# ProPrj__1__2025-03-03.net
KiCad netlist of a schematic drawn in EasyEDA Pro
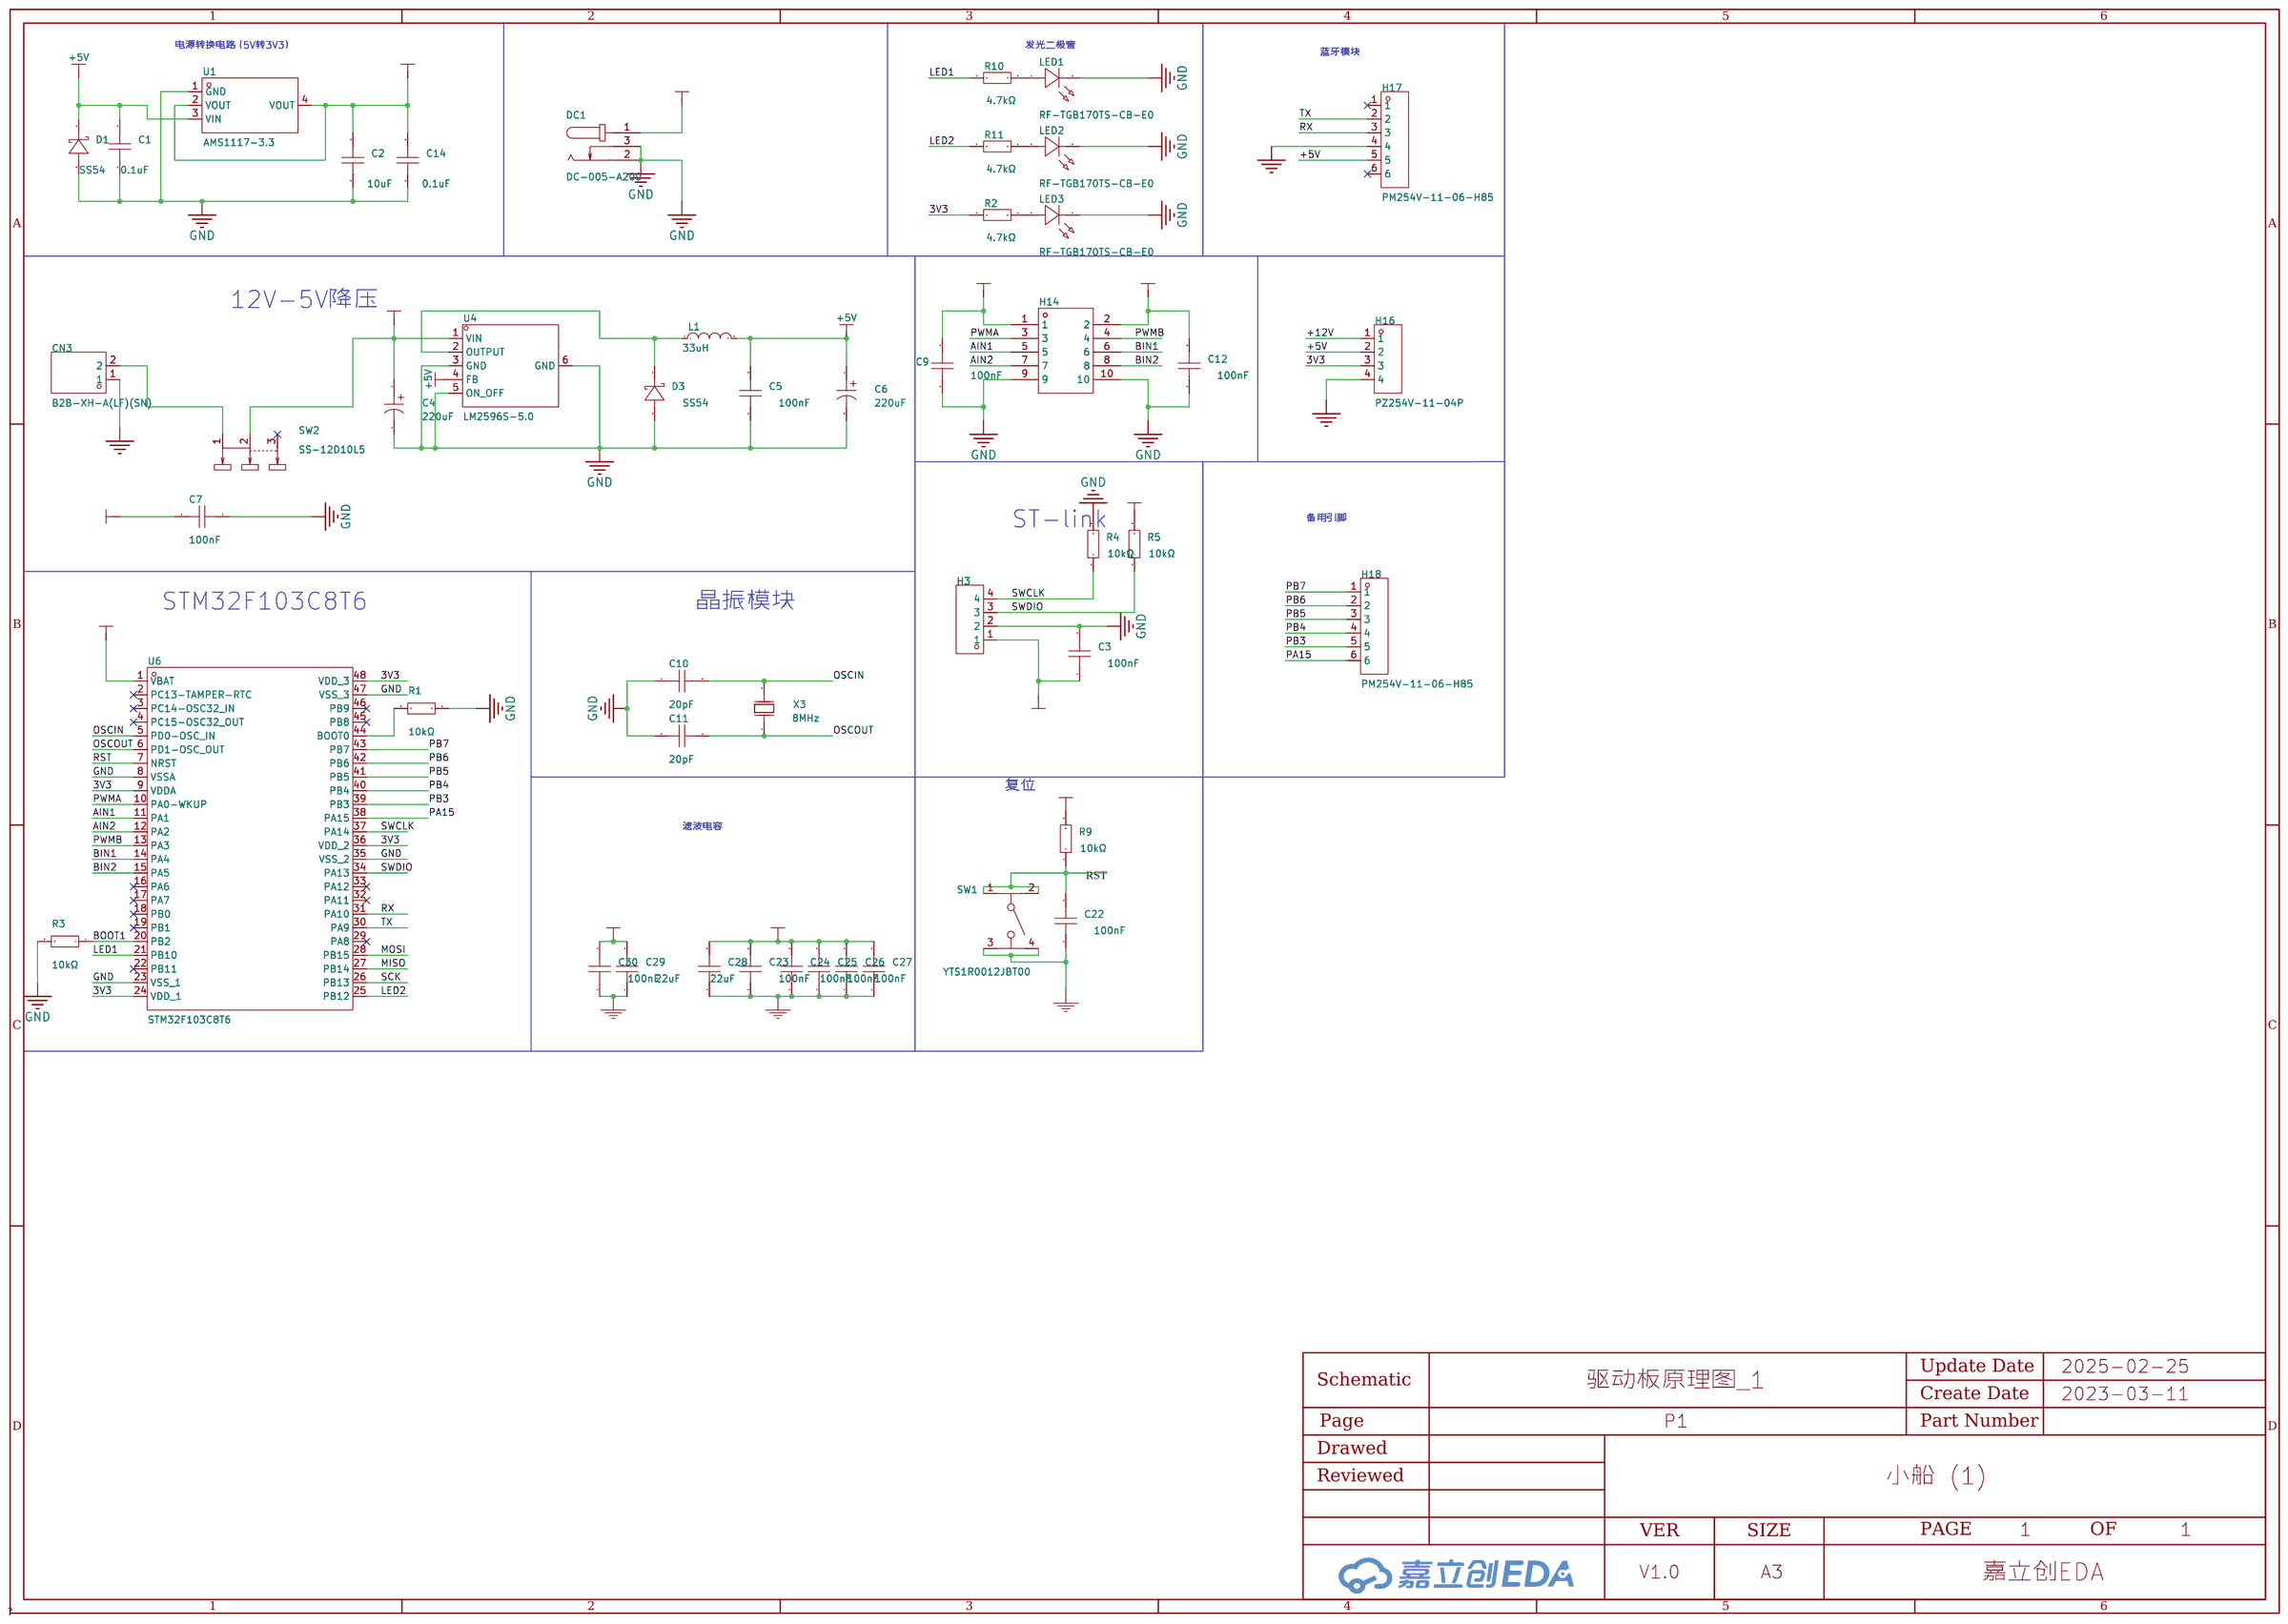
[diagram p0: schematic sheet]

(export (version "E")
  (design (tool "Eeschema 10.0.6"))
  (components
    (comp (ref "C1")
      (value "0.1uF")
      (footprint "easyedapro:C1206")
      (description "容值:47uF;精度:±20%;额定电压:16V;材质(温度系数):X5R;")
      (fields
        (field (name "Manufacturer Part") "GRM31CR61C476ME44L")
        (field (name "Manufacturer") "muRata(村田)")
      )
      (libsource (lib "easyedapro") (part "GRM31CR61C476ME44L"))
    )
    (comp (ref "C2")
      (value "10uF")
      (footprint "easyedapro:C0805")
      (description "温度系数:X7R;容值:100nF;精度:±10%;额定电压:100V;")
      (fields (field (name "Manufacturer Part") "C0805X104K101T") (field (name "Manufacturer") "IHHEC(禾伸堂)"))
      (libsource (lib "easyedapro") (part "C0805X104K101T_C485772"))
    )
    (comp (ref "C3")
      (value "100nF")
      (footprint "easyedapro:C0603")
      (description "容值:100nF;精度:-20%~+80%;额定电压:50V;材质(温度系数):Y5V;")
      (fields (field (name "Manufacturer Part") "0603F104Z500CT") (field (name "Manufacturer") "Walsin(华新科)"))
      (libsource (lib "easyedapro") (part "0603F104Z500"))
    )
    (comp (ref "C4")
      (value "220uF")
      (footprint "easyedapro:CAP-SMD_BD6.3-L6.6-W6.6-FD")
      (description "容值:220uF;额定电压:25V;")
      (fields
        (field (name "Manufacturer Part") "RX220UF25V90RV0108")
        (field (name "Manufacturer") "KNSCHA(科尼盛)")
      )
      (libsource (lib "easyedapro") (part "RX220UF25V90RV0108"))
    )
    (comp (ref "C5")
      (value "100nF")
      (footprint "easyedapro:C0805")
      (description "温度系数:X7R;容值:100nF;精度:±10%;额定电压:100V;")
      (fields (field (name "Manufacturer Part") "C0805X104K101T") (field (name "Manufacturer") "IHHEC(禾伸堂)"))
      (libsource (lib "easyedapro") (part "C0805X104K101T_C485772"))
    )
    (comp (ref "C6")
      (value "220uF")
      (footprint "easyedapro:CAP-SMD_BD6.3-L6.6-W6.6-FD")
      (description "容值:220uF;额定电压:25V;")
      (fields
        (field (name "Manufacturer Part") "RX220UF25V90RV0108")
        (field (name "Manufacturer") "KNSCHA(科尼盛)")
      )
      (libsource (lib "easyedapro") (part "RX220UF25V90RV0108"))
    )
    (comp (ref "C7")
      (value "100nF")
      (footprint "easyedapro:C0805")
      (description "温度系数:X7R;容值:100nF;精度:±10%;额定电压:100V;")
      (fields (field (name "Manufacturer Part") "C0805X104K101T") (field (name "Manufacturer") "IHHEC(禾伸堂)"))
      (libsource (lib "easyedapro") (part "C0805X104K101T_C485772"))
    )
    (comp (ref "C9")
      (value "100nF")
      (footprint "easyedapro:C0805")
      (description "温度系数:X7R;容值:100nF;精度:±10%;额定电压:100V;")
      (fields (field (name "Manufacturer Part") "C0805X104K101T") (field (name "Manufacturer") "IHHEC(禾伸堂)"))
      (libsource (lib "easyedapro") (part "C0805X104K101T_C485772"))
    )
    (comp (ref "C10")
      (value "20pF")
      (footprint "easyedapro:C0603")
      (description "容值:20pF;精度:±5%;额定电压:100V;材质(温度系数):C0G;额定电压(VAC):-;")
      (fields (field (name "Manufacturer Part") "0603CG200J101NT") (field (name "Manufacturer") "FH(风华)"))
      (libsource (lib "easyedapro") (part "0603CG200J101NT"))
    )
    (comp (ref "C11")
      (value "20pF")
      (footprint "easyedapro:C0603")
      (description "容值:20pF;精度:±5%;额定电压:100V;材质(温度系数):C0G;额定电压(VAC):-;")
      (fields (field (name "Manufacturer Part") "0603CG200J101NT") (field (name "Manufacturer") "FH(风华)"))
      (libsource (lib "easyedapro") (part "0603CG200J101NT"))
    )
    (comp (ref "C12")
      (value "100nF")
      (footprint "easyedapro:C0805")
      (description "温度系数:X7R;容值:100nF;精度:±10%;额定电压:100V;")
      (fields (field (name "Manufacturer Part") "C0805X104K101T") (field (name "Manufacturer") "IHHEC(禾伸堂)"))
      (libsource (lib "easyedapro") (part "C0805X104K101T_C485772"))
    )
    (comp (ref "C14")
      (value "0.1uF")
      (footprint "easyedapro:C1206")
      (description "容值:47uF;精度:±20%;额定电压:16V;材质(温度系数):X5R;")
      (fields
        (field (name "Manufacturer Part") "GRM31CR61C476ME44L")
        (field (name "Manufacturer") "muRata(村田)")
      )
      (libsource (lib "easyedapro") (part "GRM31CR61C476ME44L"))
    )
    (comp (ref "C22")
      (value "100nF")
      (footprint "easyedapro:C0603")
      (description "容值:100nF;精度:-20%~+80%;额定电压:50V;材质(温度系数):Y5V;")
      (fields (field (name "Manufacturer Part") "0603F104Z500CT") (field (name "Manufacturer") "Walsin(华新科)"))
      (libsource (lib "easyedapro") (part "0603F104Z500"))
    )
    (comp (ref "C23")
      (value "100nF")
      (footprint "easyedapro:C0603")
      (description "容值:100nF;精度:-20%~+80%;额定电压:50V;材质(温度系数):Y5V;")
      (fields (field (name "Manufacturer Part") "0603F104Z500CT") (field (name "Manufacturer") "Walsin(华新科)"))
      (libsource (lib "easyedapro") (part "0603F104Z500"))
    )
    (comp (ref "C24")
      (value "100nF")
      (footprint "easyedapro:C0603")
      (description "容值:100nF;精度:-20%~+80%;额定电压:50V;材质(温度系数):Y5V;")
      (fields (field (name "Manufacturer Part") "0603F104Z500CT") (field (name "Manufacturer") "Walsin(华新科)"))
      (libsource (lib "easyedapro") (part "0603F104Z500"))
    )
    (comp (ref "C25")
      (value "100nF")
      (footprint "easyedapro:C0603")
      (description "容值:100nF;精度:-20%~+80%;额定电压:50V;材质(温度系数):Y5V;")
      (fields (field (name "Manufacturer Part") "0603F104Z500CT") (field (name "Manufacturer") "Walsin(华新科)"))
      (libsource (lib "easyedapro") (part "0603F104Z500"))
    )
    (comp (ref "C26")
      (value "100nF")
      (footprint "easyedapro:C0603")
      (description "容值:100nF;精度:-20%~+80%;额定电压:50V;材质(温度系数):Y5V;")
      (fields (field (name "Manufacturer Part") "0603F104Z500CT") (field (name "Manufacturer") "Walsin(华新科)"))
      (libsource (lib "easyedapro") (part "0603F104Z500"))
    )
    (comp (ref "C27")
      (value "100nF")
      (footprint "easyedapro:C0603")
      (description "容值:100nF;精度:-20%~+80%;额定电压:50V;材质(温度系数):Y5V;")
      (fields (field (name "Manufacturer Part") "0603F104Z500CT") (field (name "Manufacturer") "Walsin(华新科)"))
      (libsource (lib "easyedapro") (part "0603F104Z500"))
    )
    (comp (ref "C28")
      (value "22uF")
      (footprint "easyedapro:C0603")
      (description "容值:22uF;精度:±20%;额定电压:4V;材质(温度系数):X5R;")
      (fields
        (field (name "Manufacturer Part") "CL10A226MR8NQNC")
        (field (name "Manufacturer") "SAMSUNG(三星)")
      )
      (libsource (lib "easyedapro") (part "CL10A226MR8NQNC"))
    )
    (comp (ref "C29")
      (value "22uF")
      (footprint "easyedapro:C0603")
      (description "容值:22uF;精度:±20%;额定电压:4V;材质(温度系数):X5R;")
      (fields
        (field (name "Manufacturer Part") "CL10A226MR8NQNC")
        (field (name "Manufacturer") "SAMSUNG(三星)")
      )
      (libsource (lib "easyedapro") (part "CL10A226MR8NQNC"))
    )
    (comp (ref "C30")
      (value "100nF")
      (footprint "easyedapro:C0603")
      (description "容值:100nF;精度:-20%~+80%;额定电压:50V;材质(温度系数):Y5V;")
      (fields (field (name "Manufacturer Part") "0603F104Z500CT") (field (name "Manufacturer") "Walsin(华新科)"))
      (libsource (lib "easyedapro") (part "0603F104Z500"))
    )
    (comp (ref "CN3")
      (value "B2B-XH-A(LF)(SN)")
      (footprint "easyedapro:CONN-TH_B2B-XH-A-LF-SN")
      (fields (field (name "Manufacturer") "JST"))
      (libsource (lib "easyedapro") (part "B2B-XH-A (LF)(SN)"))
    )
    (comp (ref "D1")
      (value "SS54")
      (footprint "easyedapro:SMA_L4.3-W2.6-LS5.0-RD")
      (fields (field (name "Manufacturer") "TWGMC(台湾迪嘉)"))
      (libsource (lib "easyedapro") (part "SS54_C727065"))
    )
    (comp (ref "D3")
      (value "SS54")
      (footprint "easyedapro:SMA_L4.3-W2.6-LS5.0-RD")
      (fields (field (name "Manufacturer") "TWGMC(台湾迪嘉)"))
      (libsource (lib "easyedapro") (part "SS54_C727065"))
    )
    (comp (ref "DC1")
      (value "DC-005-A200")
      (footprint "easyedapro:DC-IN-TH_DC-005-A200")
      (description "连接器类型:DC电源插座;安装方式:弯插;触点内径:2mm;触点外径:6.4mm;额定电流:3A;额定电压:30V;工作温度范围:-20°C~+70°C;")
      (fields (field (name "Manufacturer") "XUNPU(讯普)"))
      (libsource (lib "easyedapro") (part "DC-005-A200"))
    )
    (comp (ref "H3")
      (value "~")
      (footprint "easyedapro:HDR-TH_4P-P2.54-V-M")
      (libsource (lib "easyedapro") (part "PZ254V-11-04P"))
    )
    (comp (ref "H14")
      (value "~")
      (footprint "easyedapro:HDR-TH_10P-P2.54-V-M-R2-C5-S2.54")
      (libsource (lib "easyedapro") (part "HDR-M-2.54_2x5"))
    )
    (comp (ref "H16")
      (value "PZ254V-11-04P")
      (footprint "easyedapro:HDR-TH_4P-P2.54-V-M")
      (fields (field (name "Manufacturer") "XFCN(兴飞)"))
      (libsource (lib "easyedapro") (part "PZ254V-11-04P_C2691448"))
    )
    (comp (ref "H17")
      (value "PM254V-11-06-H85")
      (footprint "easyedapro:HDR-TH_6P-P2.54-V-F")
      (fields (field (name "Manufacturer") "XFCN(兴飞)"))
      (libsource (lib "easyedapro") (part "PM254V-11-06-H85"))
    )
    (comp (ref "H18")
      (value "PM254V-11-06-H85")
      (footprint "easyedapro:HDR-TH_6P-P2.54-V-F")
      (fields (field (name "Manufacturer") "XFCN(兴飞)"))
      (libsource (lib "easyedapro") (part "PM254V-11-06-H85"))
    )
    (comp (ref "L1")
      (value "33uH")
      (footprint "easyedapro:IND-SMD_L7.5-W7.5_CYH74")
      (description "电感值:33uH;精度:±20%;额定电流:-;饱和电流(Isat):-;直流电阻(DCR):-;类型:-;")
      (fields (field (name "Manufacturer Part") "CYH74-33UH") (field (name "Manufacturer") "SHOU HAN(首韩)"))
      (libsource (lib "easyedapro") (part "CYH74-33UH"))
    )
    (comp (ref "LED1")
      (value "RF-TGB170TS-CB-E0")
      (footprint "easyedapro:LED0805-R-RD")
      (description "发光颜色:翠绿;二极管配置:-;透镜颜色:-;主波长:-;峰值波长:-;色温:-;测试电流:20mA;功率:105mW;发光角度:140°;安装方式:正贴;工作温度:-40°C~+85°C;")
      (fields (field (name "Manufacturer") "Refond(瑞丰)"))
      (libsource (lib "easyedapro") (part "RF-TGB170TS-CB-E0"))
    )
    (comp (ref "LED2")
      (value "RF-TGB170TS-CB-E0")
      (footprint "easyedapro:LED0805-R-RD")
      (description "发光颜色:翠绿;二极管配置:-;透镜颜色:-;主波长:-;峰值波长:-;色温:-;测试电流:20mA;功率:105mW;发光角度:140°;安装方式:正贴;工作温度:-40°C~+85°C;")
      (fields (field (name "Manufacturer") "Refond(瑞丰)"))
      (libsource (lib "easyedapro") (part "RF-TGB170TS-CB-E0"))
    )
    (comp (ref "LED3")
      (value "RF-TGB170TS-CB-E0")
      (footprint "easyedapro:LED0805-R-RD")
      (description "发光颜色:翠绿;二极管配置:-;透镜颜色:-;主波长:-;峰值波长:-;色温:-;测试电流:20mA;功率:105mW;发光角度:140°;安装方式:正贴;工作温度:-40°C~+85°C;")
      (fields (field (name "Manufacturer") "Refond(瑞丰)"))
      (libsource (lib "easyedapro") (part "RF-TGB170TS-CB-E0"))
    )
    (comp (ref "R1")
      (value "10kΩ")
      (footprint "easyedapro:R0603")
      (description "精度:±1%;阻值:10kΩ;功率:1/10W;电阻类型:厚膜电阻;最大工作电压:75V;工作温度范围:-55°C~+155°C;")
      (fields (field (name "Manufacturer Part") "CR-03FA7---10K") (field (name "Manufacturer") "Viking(光颉)"))
      (libsource (lib "easyedapro") (part "CR-03FA7---10K"))
    )
    (comp (ref "R2")
      (value "4.7kΩ")
      (footprint "easyedapro:R0805")
      (description "阻值:4.7kΩ;精度:±1%;功率:125mW;")
      (fields (field (name "Manufacturer Part") "RMC08054.7K1%N") (field (name "Manufacturer") "Tyohm(幸亚电阻)"))
      (libsource (lib "easyedapro") (part "RMC08054.7K1%N"))
    )
    (comp (ref "R3")
      (value "10kΩ")
      (footprint "easyedapro:R0603")
      (description "精度:±1%;阻值:10kΩ;功率:1/10W;电阻类型:厚膜电阻;最大工作电压:75V;工作温度范围:-55°C~+155°C;")
      (fields (field (name "Manufacturer Part") "CR-03FA7---10K") (field (name "Manufacturer") "Viking(光颉)"))
      (libsource (lib "easyedapro") (part "CR-03FA7---10K"))
    )
    (comp (ref "R4")
      (value "10kΩ")
      (footprint "easyedapro:R0805")
      (description "电阻类型:厚膜电阻;阻值:10kΩ;精度:±0.5%;功率:125mW;温度系数:±100ppm/°C;最大工作电压:150V;工作温度范围:-55°C~+155°C;")
      (fields (field (name "Manufacturer Part") "RC0805DR-0710KL") (field (name "Manufacturer") "YAGEO(国巨)"))
      (libsource (lib "easyedapro") (part "RC0805DR-0710KL"))
    )
    (comp (ref "R5")
      (value "10kΩ")
      (footprint "easyedapro:R0805")
      (description "电阻类型:厚膜电阻;阻值:10kΩ;精度:±0.5%;功率:125mW;温度系数:±100ppm/°C;最大工作电压:150V;工作温度范围:-55°C~+155°C;")
      (fields (field (name "Manufacturer Part") "RC0805DR-0710KL") (field (name "Manufacturer") "YAGEO(国巨)"))
      (libsource (lib "easyedapro") (part "RC0805DR-0710KL"))
    )
    (comp (ref "R9")
      (value "10kΩ")
      (footprint "easyedapro:R0805")
      (description "电阻类型:厚膜电阻;阻值:10kΩ;精度:±0.5%;功率:125mW;温度系数:±100ppm/°C;最大工作电压:150V;工作温度范围:-55°C~+155°C;")
      (fields (field (name "Manufacturer Part") "RC0805DR-0710KL") (field (name "Manufacturer") "YAGEO(国巨)"))
      (libsource (lib "easyedapro") (part "RC0805DR-0710KL"))
    )
    (comp (ref "R10")
      (value "4.7kΩ")
      (footprint "easyedapro:R0805")
      (description "阻值:4.7kΩ;精度:±1%;功率:125mW;")
      (fields (field (name "Manufacturer Part") "RMC08054.7K1%N") (field (name "Manufacturer") "Tyohm(幸亚电阻)"))
      (libsource (lib "easyedapro") (part "RMC08054.7K1%N"))
    )
    (comp (ref "R11")
      (value "4.7kΩ")
      (footprint "easyedapro:R0805")
      (description "阻值:4.7kΩ;精度:±1%;功率:125mW;")
      (fields (field (name "Manufacturer Part") "RMC08054.7K1%N") (field (name "Manufacturer") "Tyohm(幸亚电阻)"))
      (libsource (lib "easyedapro") (part "RMC08054.7K1%N"))
    )
    (comp (ref "SW1")
      (value "YTS1R0012JBT00")
      (footprint "easyedapro:SW-TH_4P-L6.0-W6.0-P4.50-LS6.5")
      (fields (field (name "Manufacturer") "YIYUAN(怡远)"))
      (libsource (lib "easyedapro") (part "YTS1R0012JBT00"))
    )
    (comp (ref "SW2")
      (value "SS-12D10L5")
      (footprint "easyedapro:SW-TH_SS-12D10L5")
      (description "电路结构:单刀双掷;安装方式:直插;开关颜色:黑色;额定电流(DC):3A;额定电压(DC):125V;额定电流(AC):3A;额定电压(AC):125V;机械寿命:1万次;")
      (fields (field (name "Manufacturer") "XKB Connectivity(中国星坤)"))
      (libsource (lib "easyedapro") (part "SS-12D10L5"))
    )
    (comp (ref "U1")
      (value "AMS1117-3.3")
      (footprint "easyedapro:SOT-223-3_L6.5-W3.4-P2.30-LS7.0-BR")
      (fields (field (name "Manufacturer") "美国AMS"))
      (libsource (lib "easyedapro") (part "AMS1117-3.3"))
    )
    (comp (ref "U4")
      (value "LM2596S-5.0")
      (footprint "easyedapro:TO-263-5_L10.1-W8.7-P1.70-LS14.4-BR")
      (fields (field (name "Manufacturer") "Slkor(萨科微)"))
      (libsource (lib "easyedapro") (part "LM2596S-5.0_C2980820"))
    )
    (comp (ref "U6")
      (value "STM32F103C8T6")
      (footprint "easyedapro:LQFP-48_L7.0-W7.0-P0.50-LS9.0-BL")
      (fields (field (name "Manufacturer") "ST(意法半导体)"))
      (libsource (lib "easyedapro") (part "STM32F103C8T6"))
    )
    (comp (ref "X3")
      (value "8MHz")
      (footprint "easyedapro:HC-49US_L11.0-W4.6-P4.88")
      (description "晶振类型:49S晶振;频率:8MHz;频率公差:±20ppm;频率稳定度:±30ppm;负载电容:18pF;等效串联电阻(ESR):60Ω;工作温度:-40°C~+85°C;")
      (fields (field (name "Manufacturer Part") "49SAC08000182060") (field (name "Manufacturer") "JGHC(晶光华)"))
      (libsource (lib "easyedapro") (part "49SAC08000182060"))
    )
  )
  (nets
    (net (code "1") (name "+5V") (class "Default")
      (node (ref "C1") (pin "2") (pinfunction "2_2") (pintype "input"))
      (node (ref "C29") (pin "2") (pinfunction "2_2") (pintype "input"))
      (node (ref "C30") (pin "2") (pinfunction "2_2") (pintype "input"))
      (node (ref "C5") (pin "2") (pinfunction "2_2") (pintype "input"))
      (node (ref "C6") (pin "1") (pinfunction "1_1") (pintype "input"))
      (node (ref "D1") (pin "1") (pinfunction "1_1") (pintype "input"))
      (node (ref "H16") (pin "2") (pinfunction "2_2") (pintype "unspecified"))
      (node (ref "H17") (pin "5") (pinfunction "5_5") (pintype "unspecified"))
      (node (ref "L1") (pin "2") (pinfunction "2_2") (pintype "input"))
      (node (ref "U1") (pin "3") (pinfunction "VIN_3") (pintype "input"))
      (node (ref "U4") (pin "4") (pinfunction "FB_4") (pintype "input"))
    )
    (net (code "2") (name "+12V") (class "Default")
      (node (ref "C4") (pin "1") (pinfunction "1_1") (pintype "input"))
      (node (ref "C7") (pin "2") (pinfunction "2_2") (pintype "input"))
      (node (ref "DC1") (pin "1") (pinfunction "1_1") (pintype "unspecified"))
      (node (ref "H16") (pin "1") (pinfunction "1_1") (pintype "unspecified"))
      (node (ref "SW2") (pin "2") (pinfunction "2_2") (pintype "unspecified"))
      (node (ref "U4") (pin "1") (pinfunction "VIN_1") (pintype "input"))
    )
    (net (code "3") (name "/AIN1") (class "Default")
      (node (ref "H14") (pin "5") (pinfunction "5_5") (pintype "input"))
      (node (ref "U6") (pin "11") (pinfunction "PA1_11") (pintype "input"))
    )
    (net (code "4") (name "/AIN2") (class "Default")
      (node (ref "H14") (pin "7") (pinfunction "7_7") (pintype "input"))
      (node (ref "U6") (pin "12") (pinfunction "PA2_12") (pintype "input"))
    )
    (net (code "5") (name "/BIN1") (class "Default")
      (node (ref "H14") (pin "6") (pinfunction "6_6") (pintype "input"))
      (node (ref "U6") (pin "14") (pinfunction "PA4_14") (pintype "input"))
    )
    (net (code "6") (name "/BIN2") (class "Default")
      (node (ref "H14") (pin "8") (pinfunction "8_8") (pintype "input"))
      (node (ref "U6") (pin "15") (pinfunction "PA5_15") (pintype "input"))
    )
    (net (code "7") (name "/BOOT1") (class "Default")
      (node (ref "R3") (pin "1") (pinfunction "1_1") (pintype "input"))
      (node (ref "U6") (pin "20") (pinfunction "PB2_20") (pintype "input"))
    )
    (net (code "8") (name "/LED1") (class "Default")
      (node (ref "R10") (pin "1") (pinfunction "1_1") (pintype "input"))
      (node (ref "U6") (pin "21") (pinfunction "PB10_21") (pintype "input"))
    )
    (net (code "9") (name "/LED2") (class "Default")
      (node (ref "R11") (pin "1") (pinfunction "1_1") (pintype "input"))
      (node (ref "U6") (pin "25") (pinfunction "PB12_25") (pintype "input"))
    )
    (net (code "10") (name "/MISO") (class "Default")
      (node (ref "U6") (pin "27") (pinfunction "PB14_27") (pintype "input"))
    )
    (net (code "11") (name "/MOSI") (class "Default")
      (node (ref "U6") (pin "28") (pinfunction "PB15_28") (pintype "input"))
    )
    (net (code "12") (name "/OSCIN") (class "Default")
      (node (ref "C10") (pin "2") (pinfunction "2_2") (pintype "input"))
      (node (ref "U6") (pin "5") (pinfunction "PD0-OSC_IN_5") (pintype "input"))
      (node (ref "X3") (pin "2") (pinfunction "OSC2_2") (pintype "input"))
    )
    (net (code "13") (name "/OSCOUT") (class "Default")
      (node (ref "C11") (pin "2") (pinfunction "2_2") (pintype "input"))
      (node (ref "U6") (pin "6") (pinfunction "PD1-OSC_OUT_6") (pintype "input"))
      (node (ref "X3") (pin "1") (pinfunction "OSC1_1") (pintype "input"))
    )
    (net (code "14") (name "/PA15") (class "Default")
      (node (ref "H18") (pin "6") (pinfunction "6_6") (pintype "unspecified"))
      (node (ref "U6") (pin "38") (pinfunction "PA15_38") (pintype "input"))
    )
    (net (code "15") (name "/PB3") (class "Default")
      (node (ref "H18") (pin "5") (pinfunction "5_5") (pintype "unspecified"))
      (node (ref "U6") (pin "39") (pinfunction "PB3_39") (pintype "input"))
    )
    (net (code "16") (name "/PB4") (class "Default")
      (node (ref "H18") (pin "4") (pinfunction "4_4") (pintype "unspecified"))
      (node (ref "U6") (pin "40") (pinfunction "PB4_40") (pintype "input"))
    )
    (net (code "17") (name "/PB5") (class "Default")
      (node (ref "H18") (pin "3") (pinfunction "3_3") (pintype "unspecified"))
      (node (ref "U6") (pin "41") (pinfunction "PB5_41") (pintype "input"))
    )
    (net (code "18") (name "/PB6") (class "Default")
      (node (ref "H18") (pin "2") (pinfunction "2_2") (pintype "unspecified"))
      (node (ref "U6") (pin "42") (pinfunction "PB6_42") (pintype "input"))
    )
    (net (code "19") (name "/PB7") (class "Default")
      (node (ref "H18") (pin "1") (pinfunction "1_1") (pintype "unspecified"))
      (node (ref "U6") (pin "43") (pinfunction "PB7_43") (pintype "input"))
    )
    (net (code "20") (name "/PWMA") (class "Default")
      (node (ref "H14") (pin "3") (pinfunction "3_3") (pintype "input"))
      (node (ref "U6") (pin "10") (pinfunction "PA0-WKUP_10") (pintype "input"))
    )
    (net (code "21") (name "/PWMB") (class "Default")
      (node (ref "H14") (pin "4") (pinfunction "4_4") (pintype "input"))
      (node (ref "U6") (pin "13") (pinfunction "PA3_13") (pintype "input"))
    )
    (net (code "22") (name "/RST") (class "Default")
      (node (ref "C22") (pin "2") (pinfunction "2_2") (pintype "input"))
      (node (ref "R9") (pin "1") (pinfunction "1_1") (pintype "input"))
      (node (ref "SW1") (pin "1") (pinfunction "1_1") (pintype "input"))
      (node (ref "SW1") (pin "2") (pinfunction "2_2") (pintype "input"))
      (node (ref "U6") (pin "7") (pinfunction "NRST_7") (pintype "input"))
    )
    (net (code "23") (name "/RX") (class "Default")
      (node (ref "H17") (pin "3") (pinfunction "3_3") (pintype "unspecified"))
      (node (ref "U6") (pin "31") (pinfunction "PA10_31") (pintype "input"))
    )
    (net (code "24") (name "/SCK") (class "Default")
      (node (ref "U6") (pin "26") (pinfunction "PB13_26") (pintype "input"))
    )
    (net (code "25") (name "/SWCLK") (class "Default")
      (node (ref "H3") (pin "4") (pinfunction "4_4") (pintype "input"))
      (node (ref "R4") (pin "1") (pinfunction "1_1") (pintype "input"))
      (node (ref "U6") (pin "37") (pinfunction "PA14_37") (pintype "input"))
    )
    (net (code "26") (name "/SWDIO") (class "Default")
      (node (ref "H3") (pin "3") (pinfunction "3_3") (pintype "input"))
      (node (ref "R5") (pin "1") (pinfunction "1_1") (pintype "input"))
      (node (ref "U6") (pin "34") (pinfunction "PA13_34") (pintype "input"))
    )
    (net (code "27") (name "/TX") (class "Default")
      (node (ref "H17") (pin "2") (pinfunction "2_2") (pintype "unspecified"))
      (node (ref "U6") (pin "30") (pinfunction "PA9_30") (pintype "input"))
    )
    (net (code "28") (name "3V3") (class "Default")
      (node (ref "C12") (pin "2") (pinfunction "2_2") (pintype "input"))
      (node (ref "C14") (pin "2") (pinfunction "2_2") (pintype "input"))
      (node (ref "C2") (pin "2") (pinfunction "2_2") (pintype "input"))
      (node (ref "C23") (pin "2") (pinfunction "2_2") (pintype "input"))
      (node (ref "C24") (pin "2") (pinfunction "2_2") (pintype "input"))
      (node (ref "C25") (pin "2") (pinfunction "2_2") (pintype "input"))
      (node (ref "C26") (pin "2") (pinfunction "2_2") (pintype "input"))
      (node (ref "C27") (pin "2") (pinfunction "2_2") (pintype "input"))
      (node (ref "C28") (pin "2") (pinfunction "2_2") (pintype "input"))
      (node (ref "C3") (pin "1") (pinfunction "1_1") (pintype "input"))
      (node (ref "C9") (pin "2") (pinfunction "2_2") (pintype "input"))
      (node (ref "H14") (pin "1") (pinfunction "1_1") (pintype "input"))
      (node (ref "H14") (pin "2") (pinfunction "2_2") (pintype "input"))
      (node (ref "H16") (pin "3") (pinfunction "3_3") (pintype "unspecified"))
      (node (ref "H3") (pin "1") (pinfunction "1_1") (pintype "input"))
      (node (ref "R2") (pin "1") (pinfunction "1_1") (pintype "input"))
      (node (ref "R5") (pin "2") (pinfunction "2_2") (pintype "input"))
      (node (ref "R9") (pin "2") (pinfunction "2_2") (pintype "input"))
      (node (ref "U1") (pin "2") (pinfunction "VOUT_2") (pintype "input"))
      (node (ref "U1") (pin "4") (pinfunction "VOUT_4") (pintype "input"))
      (node (ref "U6") (pin "1") (pinfunction "VBAT_1") (pintype "input"))
      (node (ref "U6") (pin "24") (pinfunction "VDD_1_24") (pintype "input"))
      (node (ref "U6") (pin "36") (pinfunction "VDD_2_36") (pintype "input"))
      (node (ref "U6") (pin "48") (pinfunction "VDD_3_48") (pintype "input"))
      (node (ref "U6") (pin "9") (pinfunction "VDDA_9") (pintype "input"))
    )
    (net (code "29") (name "GND") (class "Default")
      (node (ref "C1") (pin "1") (pinfunction "1_1") (pintype "input"))
      (node (ref "C10") (pin "1") (pinfunction "1_1") (pintype "input"))
      (node (ref "C11") (pin "1") (pinfunction "1_1") (pintype "input"))
      (node (ref "C12") (pin "1") (pinfunction "1_1") (pintype "input"))
      (node (ref "C14") (pin "1") (pinfunction "1_1") (pintype "input"))
      (node (ref "C2") (pin "1") (pinfunction "1_1") (pintype "input"))
      (node (ref "C22") (pin "1") (pinfunction "1_1") (pintype "input"))
      (node (ref "C23") (pin "1") (pinfunction "1_1") (pintype "input"))
      (node (ref "C24") (pin "1") (pinfunction "1_1") (pintype "input"))
      (node (ref "C25") (pin "1") (pinfunction "1_1") (pintype "input"))
      (node (ref "C26") (pin "1") (pinfunction "1_1") (pintype "input"))
      (node (ref "C27") (pin "1") (pinfunction "1_1") (pintype "input"))
      (node (ref "C28") (pin "1") (pinfunction "1_1") (pintype "input"))
      (node (ref "C29") (pin "1") (pinfunction "1_1") (pintype "input"))
      (node (ref "C3") (pin "2") (pinfunction "2_2") (pintype "input"))
      (node (ref "C30") (pin "1") (pinfunction "1_1") (pintype "input"))
      (node (ref "C4") (pin "2") (pinfunction "2_2") (pintype "input"))
      (node (ref "C5") (pin "1") (pinfunction "1_1") (pintype "input"))
      (node (ref "C6") (pin "2") (pinfunction "2_2") (pintype "input"))
      (node (ref "C7") (pin "1") (pinfunction "1_1") (pintype "input"))
      (node (ref "C9") (pin "1") (pinfunction "1_1") (pintype "input"))
      (node (ref "CN3") (pin "1") (pinfunction "1_1") (pintype "unspecified"))
      (node (ref "D1") (pin "2") (pinfunction "2_2") (pintype "input"))
      (node (ref "D3") (pin "2") (pinfunction "2_2") (pintype "input"))
      (node (ref "DC1") (pin "2") (pinfunction "2_2") (pintype "unspecified"))
      (node (ref "DC1") (pin "3") (pinfunction "3_3") (pintype "unspecified"))
      (node (ref "H14") (pin "10") (pinfunction "10_10") (pintype "input"))
      (node (ref "H14") (pin "9") (pinfunction "9_9") (pintype "input"))
      (node (ref "H16") (pin "4") (pinfunction "4_4") (pintype "unspecified"))
      (node (ref "H17") (pin "4") (pinfunction "4_4") (pintype "unspecified"))
      (node (ref "H3") (pin "2") (pinfunction "2_2") (pintype "input"))
      (node (ref "LED1") (pin "2") (pinfunction "2_2") (pintype "input"))
      (node (ref "LED2") (pin "2") (pinfunction "2_2") (pintype "input"))
      (node (ref "LED3") (pin "2") (pinfunction "2_2") (pintype "input"))
      (node (ref "R1") (pin "1") (pinfunction "1_1") (pintype "input"))
      (node (ref "R3") (pin "2") (pinfunction "2_2") (pintype "input"))
      (node (ref "R4") (pin "2") (pinfunction "2_2") (pintype "input"))
      (node (ref "SW1") (pin "3") (pinfunction "3_3") (pintype "input"))
      (node (ref "SW1") (pin "4") (pinfunction "4_4") (pintype "input"))
      (node (ref "U1") (pin "1") (pinfunction "GND_1") (pintype "input"))
      (node (ref "U4") (pin "3") (pinfunction "GND_3") (pintype "input"))
      (node (ref "U4") (pin "5") (pinfunction "ON_OFF_5") (pintype "input"))
      (node (ref "U4") (pin "6") (pinfunction "GND_6") (pintype "input"))
      (node (ref "U6") (pin "23") (pinfunction "VSS_1_23") (pintype "input"))
      (node (ref "U6") (pin "35") (pinfunction "VSS_2_35") (pintype "input"))
      (node (ref "U6") (pin "47") (pinfunction "VSS_3_47") (pintype "input"))
      (node (ref "U6") (pin "8") (pinfunction "VSSA_8") (pintype "input"))
    )
    (net (code "30") (name "Net-(CN3-Pad2)") (class "Default")
      (node (ref "CN3") (pin "2") (pinfunction "2_2") (pintype "unspecified"))
      (node (ref "SW2") (pin "1") (pinfunction "1_1") (pintype "unspecified"))
    )
    (net (code "31") (name "Net-(LED1-Pad1)") (class "Default")
      (node (ref "LED1") (pin "1") (pinfunction "1_1") (pintype "input"))
      (node (ref "R10") (pin "2") (pinfunction "2_2") (pintype "input"))
    )
    (net (code "32") (name "Net-(LED2-Pad1)") (class "Default")
      (node (ref "LED2") (pin "1") (pinfunction "1_1") (pintype "input"))
      (node (ref "R11") (pin "2") (pinfunction "2_2") (pintype "input"))
    )
    (net (code "33") (name "Net-(LED3-Pad1)") (class "Default")
      (node (ref "LED3") (pin "1") (pinfunction "1_1") (pintype "input"))
      (node (ref "R2") (pin "2") (pinfunction "2_2") (pintype "input"))
    )
    (net (code "34") (name "Net-(U4-OUTPUT)") (class "Default")
      (node (ref "D3") (pin "1") (pinfunction "1_1") (pintype "input"))
      (node (ref "L1") (pin "1") (pinfunction "1_1") (pintype "input"))
      (node (ref "U4") (pin "2") (pinfunction "OUTPUT_2") (pintype "input"))
    )
    (net (code "35") (name "Net-(U6-BOOT0)") (class "Default")
      (node (ref "R1") (pin "2") (pinfunction "2_2") (pintype "input"))
      (node (ref "U6") (pin "44") (pinfunction "BOOT0_44") (pintype "input"))
    )
    (net (code "36") (name "unconnected-(H17-Pad1)") (class "Default")
      (node (ref "H17") (pin "1") (pinfunction "1_1") (pintype "unspecified+no_connect"))
    )
    (net (code "37") (name "unconnected-(H17-Pad6)") (class "Default")
      (node (ref "H17") (pin "6") (pinfunction "6_6") (pintype "unspecified+no_connect"))
    )
    (net (code "38") (name "unconnected-(SW2-Pad3)") (class "Default")
      (node (ref "SW2") (pin "3") (pinfunction "3_3") (pintype "unspecified+no_connect"))
    )
    (net (code "39") (name "unconnected-(U6-PA6-Pad16)") (class "Default")
      (node (ref "U6") (pin "16") (pinfunction "PA6_16") (pintype "input+no_connect"))
    )
    (net (code "40") (name "unconnected-(U6-PA7-Pad17)") (class "Default")
      (node (ref "U6") (pin "17") (pinfunction "PA7_17") (pintype "input+no_connect"))
    )
    (net (code "41") (name "unconnected-(U6-PA8-Pad29)") (class "Default")
      (node (ref "U6") (pin "29") (pinfunction "PA8_29") (pintype "input+no_connect"))
    )
    (net (code "42") (name "unconnected-(U6-PA11-Pad32)") (class "Default")
      (node (ref "U6") (pin "32") (pinfunction "PA11_32") (pintype "input+no_connect"))
    )
    (net (code "43") (name "unconnected-(U6-PA12-Pad33)") (class "Default")
      (node (ref "U6") (pin "33") (pinfunction "PA12_33") (pintype "input+no_connect"))
    )
    (net (code "44") (name "unconnected-(U6-PB0-Pad18)") (class "Default")
      (node (ref "U6") (pin "18") (pinfunction "PB0_18") (pintype "input+no_connect"))
    )
    (net (code "45") (name "unconnected-(U6-PB1-Pad19)") (class "Default")
      (node (ref "U6") (pin "19") (pinfunction "PB1_19") (pintype "input+no_connect"))
    )
    (net (code "46") (name "unconnected-(U6-PB8-Pad45)") (class "Default")
      (node (ref "U6") (pin "45") (pinfunction "PB8_45") (pintype "input+no_connect"))
    )
    (net (code "47") (name "unconnected-(U6-PB9-Pad46)") (class "Default")
      (node (ref "U6") (pin "46") (pinfunction "PB9_46") (pintype "input+no_connect"))
    )
    (net (code "48") (name "unconnected-(U6-PB11-Pad22)") (class "Default")
      (node (ref "U6") (pin "22") (pinfunction "PB11_22") (pintype "input+no_connect"))
    )
    (net (code "49") (name "unconnected-(U6-PC13-TAMPER-RTC-Pad2)") (class "Default")
      (node (ref "U6") (pin "2") (pinfunction "PC13-TAMPER-RTC_2") (pintype "input+no_connect"))
    )
    (net (code "50") (name "unconnected-(U6-PC14-OSC32_IN-Pad3)") (class "Default")
      (node (ref "U6") (pin "3") (pinfunction "PC14-OSC32_IN_3") (pintype "input+no_connect"))
    )
    (net (code "51") (name "unconnected-(U6-PC15-OSC32_OUT-Pad4)") (class "Default")
      (node (ref "U6") (pin "4") (pinfunction "PC15-OSC32_OUT_4") (pintype "input+no_connect"))
    )
  )
)
